# TinyBuddy-rev1.net
KiCad netlist of a schematic drawn in EAGLE
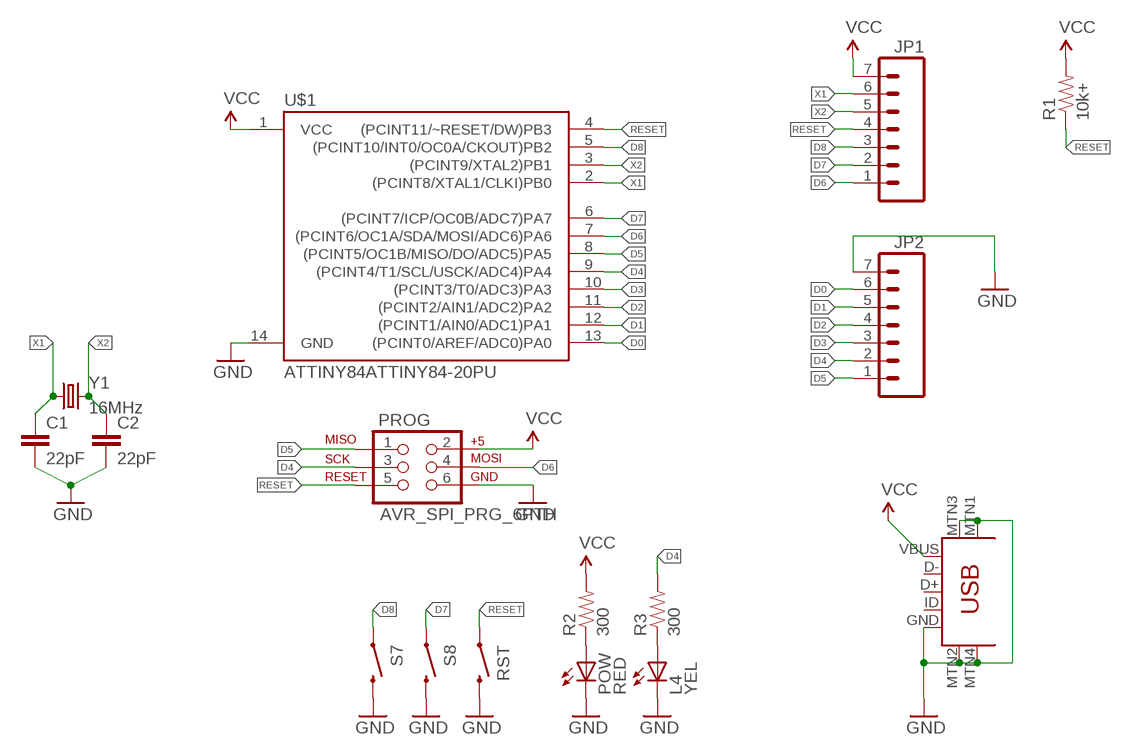
[diagram p0: schematic, sheet 1]

(export (version "E")
  (design (tool "Eeschema 10.0.6"))
  (components
    (comp (ref "C1")
      (value "22pF")
      (footprint "eagle-import:CAP-PTH-SMALL")
      (libsource (lib "eagle-import") (part "CAPPTH"))
    )
    (comp (ref "C2")
      (value "22pF")
      (footprint "eagle-import:CAP-PTH-SMALL")
      (libsource (lib "eagle-import") (part "CAPPTH"))
    )
    (comp (ref "JP1")
      (value "M07NOSILK")
      (footprint "eagle-import:1X07_NOSILK")
      (libsource (lib "eagle-import") (part "M07NOSILK"))
    )
    (comp (ref "JP2")
      (value "M07NOSILK")
      (footprint "eagle-import:1X07_NOSILK")
      (libsource (lib "eagle-import") (part "M07NOSILK"))
    )
    (comp (ref "L4")
      (value "YEL")
      (footprint "eagle-import:LED3MM")
      (libsource (lib "eagle-import") (part "LED3MM"))
    )
    (comp (ref "POW")
      (value "RED")
      (footprint "eagle-import:LED3MM")
      (libsource (lib "eagle-import") (part "LED3MM"))
    )
    (comp (ref "PROG")
      (value "AVR_SPI_PRG_6PTH")
      (footprint "eagle-import:2X3")
      (libsource (lib "eagle-import") (part "AVR_SPI_PRG_6PTH"))
    )
    (comp (ref "R1")
      (value "10k+")
      (footprint "eagle-import:1_6W-RES")
      (libsource (lib "eagle-import") (part "RESISTORPTH-1/6W"))
    )
    (comp (ref "R2")
      (value "300")
      (footprint "eagle-import:1_6W-RES")
      (libsource (lib "eagle-import") (part "RESISTORPTH-1/6W"))
    )
    (comp (ref "R3")
      (value "300")
      (footprint "eagle-import:1_6W-RES")
      (libsource (lib "eagle-import") (part "RESISTORPTH-1/6W"))
    )
    (comp (ref "RST")
      (value "SWITCH-MOMENTARY-2PTH")
      (footprint "eagle-import:TACTILE-PTH")
      (libsource (lib "eagle-import") (part "SWITCH-MOMENTARY-2PTH"))
    )
    (comp (ref "S7")
      (value "SWITCH-MOMENTARY-2PTH")
      (footprint "eagle-import:TACTILE-PTH")
      (libsource (lib "eagle-import") (part "SWITCH-MOMENTARY-2PTH"))
    )
    (comp (ref "S8")
      (value "SWITCH-MOMENTARY-2PTH")
      (footprint "eagle-import:TACTILE-PTH")
      (libsource (lib "eagle-import") (part "SWITCH-MOMENTARY-2PTH"))
    )
    (comp (ref "U$1")
      (value "ATTINY84ATTINY84-20PU")
      (footprint "eagle-import:DIL14")
      (libsource (lib "eagle-import") (part "ATTINY84ATTINY84-20PU"))
    )
    (comp (ref "U$2")
      (value "USB-MINIB-5PIN")
      (footprint "eagle-import:USB-MINIB")
      (libsource (lib "eagle-import") (part "USB-MINIB-5PIN"))
    )
    (comp (ref "Y1")
      (value "16MHz")
      (footprint "eagle-import:HC49US")
      (libsource (lib "eagle-import") (part "CRYSTALHC49US"))
    )
  )
  (nets
    (net (code "1") (name "D0") (class "Default")
      (node (ref "JP2") (pin "6") (pinfunction "6_6") (pintype "passive"))
      (node (ref "U$1") (pin "13") (pinfunction "(PCINT0/AREF/ADC0)PA0_13") (pintype "bidirectional"))
    )
    (net (code "2") (name "D1") (class "Default")
      (node (ref "JP2") (pin "5") (pinfunction "5_5") (pintype "passive"))
      (node (ref "U$1") (pin "12") (pinfunction "(PCINT1/AIN0/ADC1)PA1_12") (pintype "bidirectional"))
    )
    (net (code "3") (name "D2") (class "Default")
      (node (ref "JP2") (pin "4") (pinfunction "4_4") (pintype "passive"))
      (node (ref "U$1") (pin "11") (pinfunction "(PCINT2/AIN1/ADC2)PA2_11") (pintype "bidirectional"))
    )
    (net (code "4") (name "D3") (class "Default")
      (node (ref "JP2") (pin "3") (pinfunction "3_3") (pintype "passive"))
      (node (ref "U$1") (pin "10") (pinfunction "(PCINT3/T0/ADC3)PA3_10") (pintype "bidirectional"))
    )
    (net (code "5") (name "D4") (class "Default")
      (node (ref "JP2") (pin "2") (pinfunction "2_2") (pintype "passive"))
      (node (ref "PROG") (pin "3") (pinfunction "3_3") (pintype "passive"))
      (node (ref "R3") (pin "2") (pinfunction "2_2") (pintype "passive"))
      (node (ref "U$1") (pin "9") (pinfunction "(PCINT4/T1/SCL/USCK/ADC4)PA4_9") (pintype "bidirectional"))
    )
    (net (code "6") (name "D5") (class "Default")
      (node (ref "JP2") (pin "1") (pinfunction "1_1") (pintype "passive"))
      (node (ref "PROG") (pin "1") (pinfunction "1_1") (pintype "passive"))
      (node (ref "U$1") (pin "8") (pinfunction "(PCINT5/OC1B/MISO/DO/ADC5)PA5_8") (pintype "bidirectional"))
    )
    (net (code "7") (name "D6") (class "Default")
      (node (ref "JP1") (pin "1") (pinfunction "1_1") (pintype "passive"))
      (node (ref "PROG") (pin "4") (pinfunction "4_4") (pintype "passive"))
      (node (ref "U$1") (pin "7") (pinfunction "(PCINT6/OC1A/SDA/MOSI/ADC6)PA6_7") (pintype "bidirectional"))
    )
    (net (code "8") (name "D7") (class "Default")
      (node (ref "JP1") (pin "2") (pinfunction "2_2") (pintype "passive"))
      (node (ref "S8") (pin "1") (pinfunction "1_1") (pintype "passive"))
      (node (ref "U$1") (pin "6") (pinfunction "(PCINT7/ICP/OC0B/ADC7)PA7_6") (pintype "bidirectional"))
    )
    (net (code "9") (name "D8") (class "Default")
      (node (ref "JP1") (pin "3") (pinfunction "3_3") (pintype "passive"))
      (node (ref "S7") (pin "1") (pinfunction "1_1") (pintype "passive"))
      (node (ref "U$1") (pin "5") (pinfunction "(PCINT10/INT0/OC0A/CKOUT)PB2_5") (pintype "bidirectional"))
    )
    (net (code "10") (name "GND") (class "Default")
      (node (ref "C1") (pin "2") (pinfunction "2_2") (pintype "passive"))
      (node (ref "C2") (pin "2") (pinfunction "2_2") (pintype "passive"))
      (node (ref "JP2") (pin "7") (pinfunction "7_7") (pintype "passive"))
      (node (ref "L4") (pin "K") (pinfunction "C_K") (pintype "passive"))
      (node (ref "POW") (pin "K") (pinfunction "C_K") (pintype "passive"))
      (node (ref "PROG") (pin "6") (pinfunction "6_6") (pintype "passive"))
      (node (ref "RST") (pin "3") (pinfunction "2_3") (pintype "passive"))
      (node (ref "S7") (pin "3") (pinfunction "2_3") (pintype "passive"))
      (node (ref "S8") (pin "3") (pinfunction "2_3") (pintype "passive"))
      (node (ref "U$1") (pin "14") (pinfunction "GND_14") (pintype "bidirectional"))
      (node (ref "U$2") (pin "GND") (pinfunction "GND_GND") (pintype "bidirectional"))
      (node (ref "U$2") (pin "MTN1") (pinfunction "MTN2_MTN1") (pintype "bidirectional"))
      (node (ref "U$2") (pin "MTN2") (pinfunction "MTN3_MTN2") (pintype "bidirectional"))
      (node (ref "U$2") (pin "MTN3") (pinfunction "MTN1_MTN3") (pintype "bidirectional"))
      (node (ref "U$2") (pin "MTN4") (pinfunction "MTN4_MTN4") (pintype "bidirectional"))
    )
    (net (code "11") (name "Net-(L4-PadA)") (class "Default")
      (node (ref "L4") (pin "A") (pinfunction "A_A") (pintype "passive"))
      (node (ref "R3") (pin "1") (pinfunction "1_1") (pintype "passive"))
    )
    (net (code "12") (name "Net-(POW-PadA)") (class "Default")
      (node (ref "POW") (pin "A") (pinfunction "A_A") (pintype "passive"))
      (node (ref "R2") (pin "1") (pinfunction "1_1") (pintype "passive"))
    )
    (net (code "13") (name "RESET") (class "Default")
      (node (ref "JP1") (pin "4") (pinfunction "4_4") (pintype "passive"))
      (node (ref "PROG") (pin "5") (pinfunction "5_5") (pintype "passive"))
      (node (ref "R1") (pin "1") (pinfunction "1_1") (pintype "passive"))
      (node (ref "RST") (pin "1") (pinfunction "1_1") (pintype "passive"))
      (node (ref "U$1") (pin "4") (pinfunction "(PCINT11/~{RESET/DW})PB3_4") (pintype "bidirectional"))
    )
    (net (code "14") (name "VCC") (class "Default")
      (node (ref "JP1") (pin "7") (pinfunction "7_7") (pintype "passive"))
      (node (ref "PROG") (pin "2") (pinfunction "2_2") (pintype "passive"))
      (node (ref "R1") (pin "2") (pinfunction "2_2") (pintype "passive"))
      (node (ref "R2") (pin "2") (pinfunction "2_2") (pintype "passive"))
      (node (ref "U$1") (pin "1") (pinfunction "VCC_1") (pintype "bidirectional"))
      (node (ref "U$2") (pin "VBUS") (pinfunction "VBUS_VBUS") (pintype "bidirectional"))
    )
    (net (code "15") (name "X1") (class "Default")
      (node (ref "C1") (pin "1") (pinfunction "1_1") (pintype "passive"))
      (node (ref "JP1") (pin "6") (pinfunction "6_6") (pintype "passive"))
      (node (ref "U$1") (pin "2") (pinfunction "(PCINT8/XTAL1/CLKI)PB0_2") (pintype "bidirectional"))
      (node (ref "Y1") (pin "1") (pinfunction "1_1") (pintype "passive"))
    )
    (net (code "16") (name "X2") (class "Default")
      (node (ref "C2") (pin "1") (pinfunction "1_1") (pintype "passive"))
      (node (ref "JP1") (pin "5") (pinfunction "5_5") (pintype "passive"))
      (node (ref "U$1") (pin "3") (pinfunction "(PCINT9/XTAL2)PB1_3") (pintype "bidirectional"))
      (node (ref "Y1") (pin "2") (pinfunction "2_2") (pintype "passive"))
    )
    (net (code "17") (name "unconnected-(U$2-PadD+)") (class "Default")
      (node (ref "U$2") (pin "D+") (pinfunction "D+_D+") (pintype "bidirectional"))
    )
    (net (code "18") (name "unconnected-(U$2-PadD-)") (class "Default")
      (node (ref "U$2") (pin "D-") (pinfunction "D-_D-") (pintype "bidirectional"))
    )
    (net (code "19") (name "unconnected-(U$2-PadID)") (class "Default")
      (node (ref "U$2") (pin "ID") (pinfunction "ID_ID") (pintype "bidirectional"))
    )
  )
)
